# DBG_BOOT_CONF.net
KiCad netlist of a schematic drawn in Altium Designer
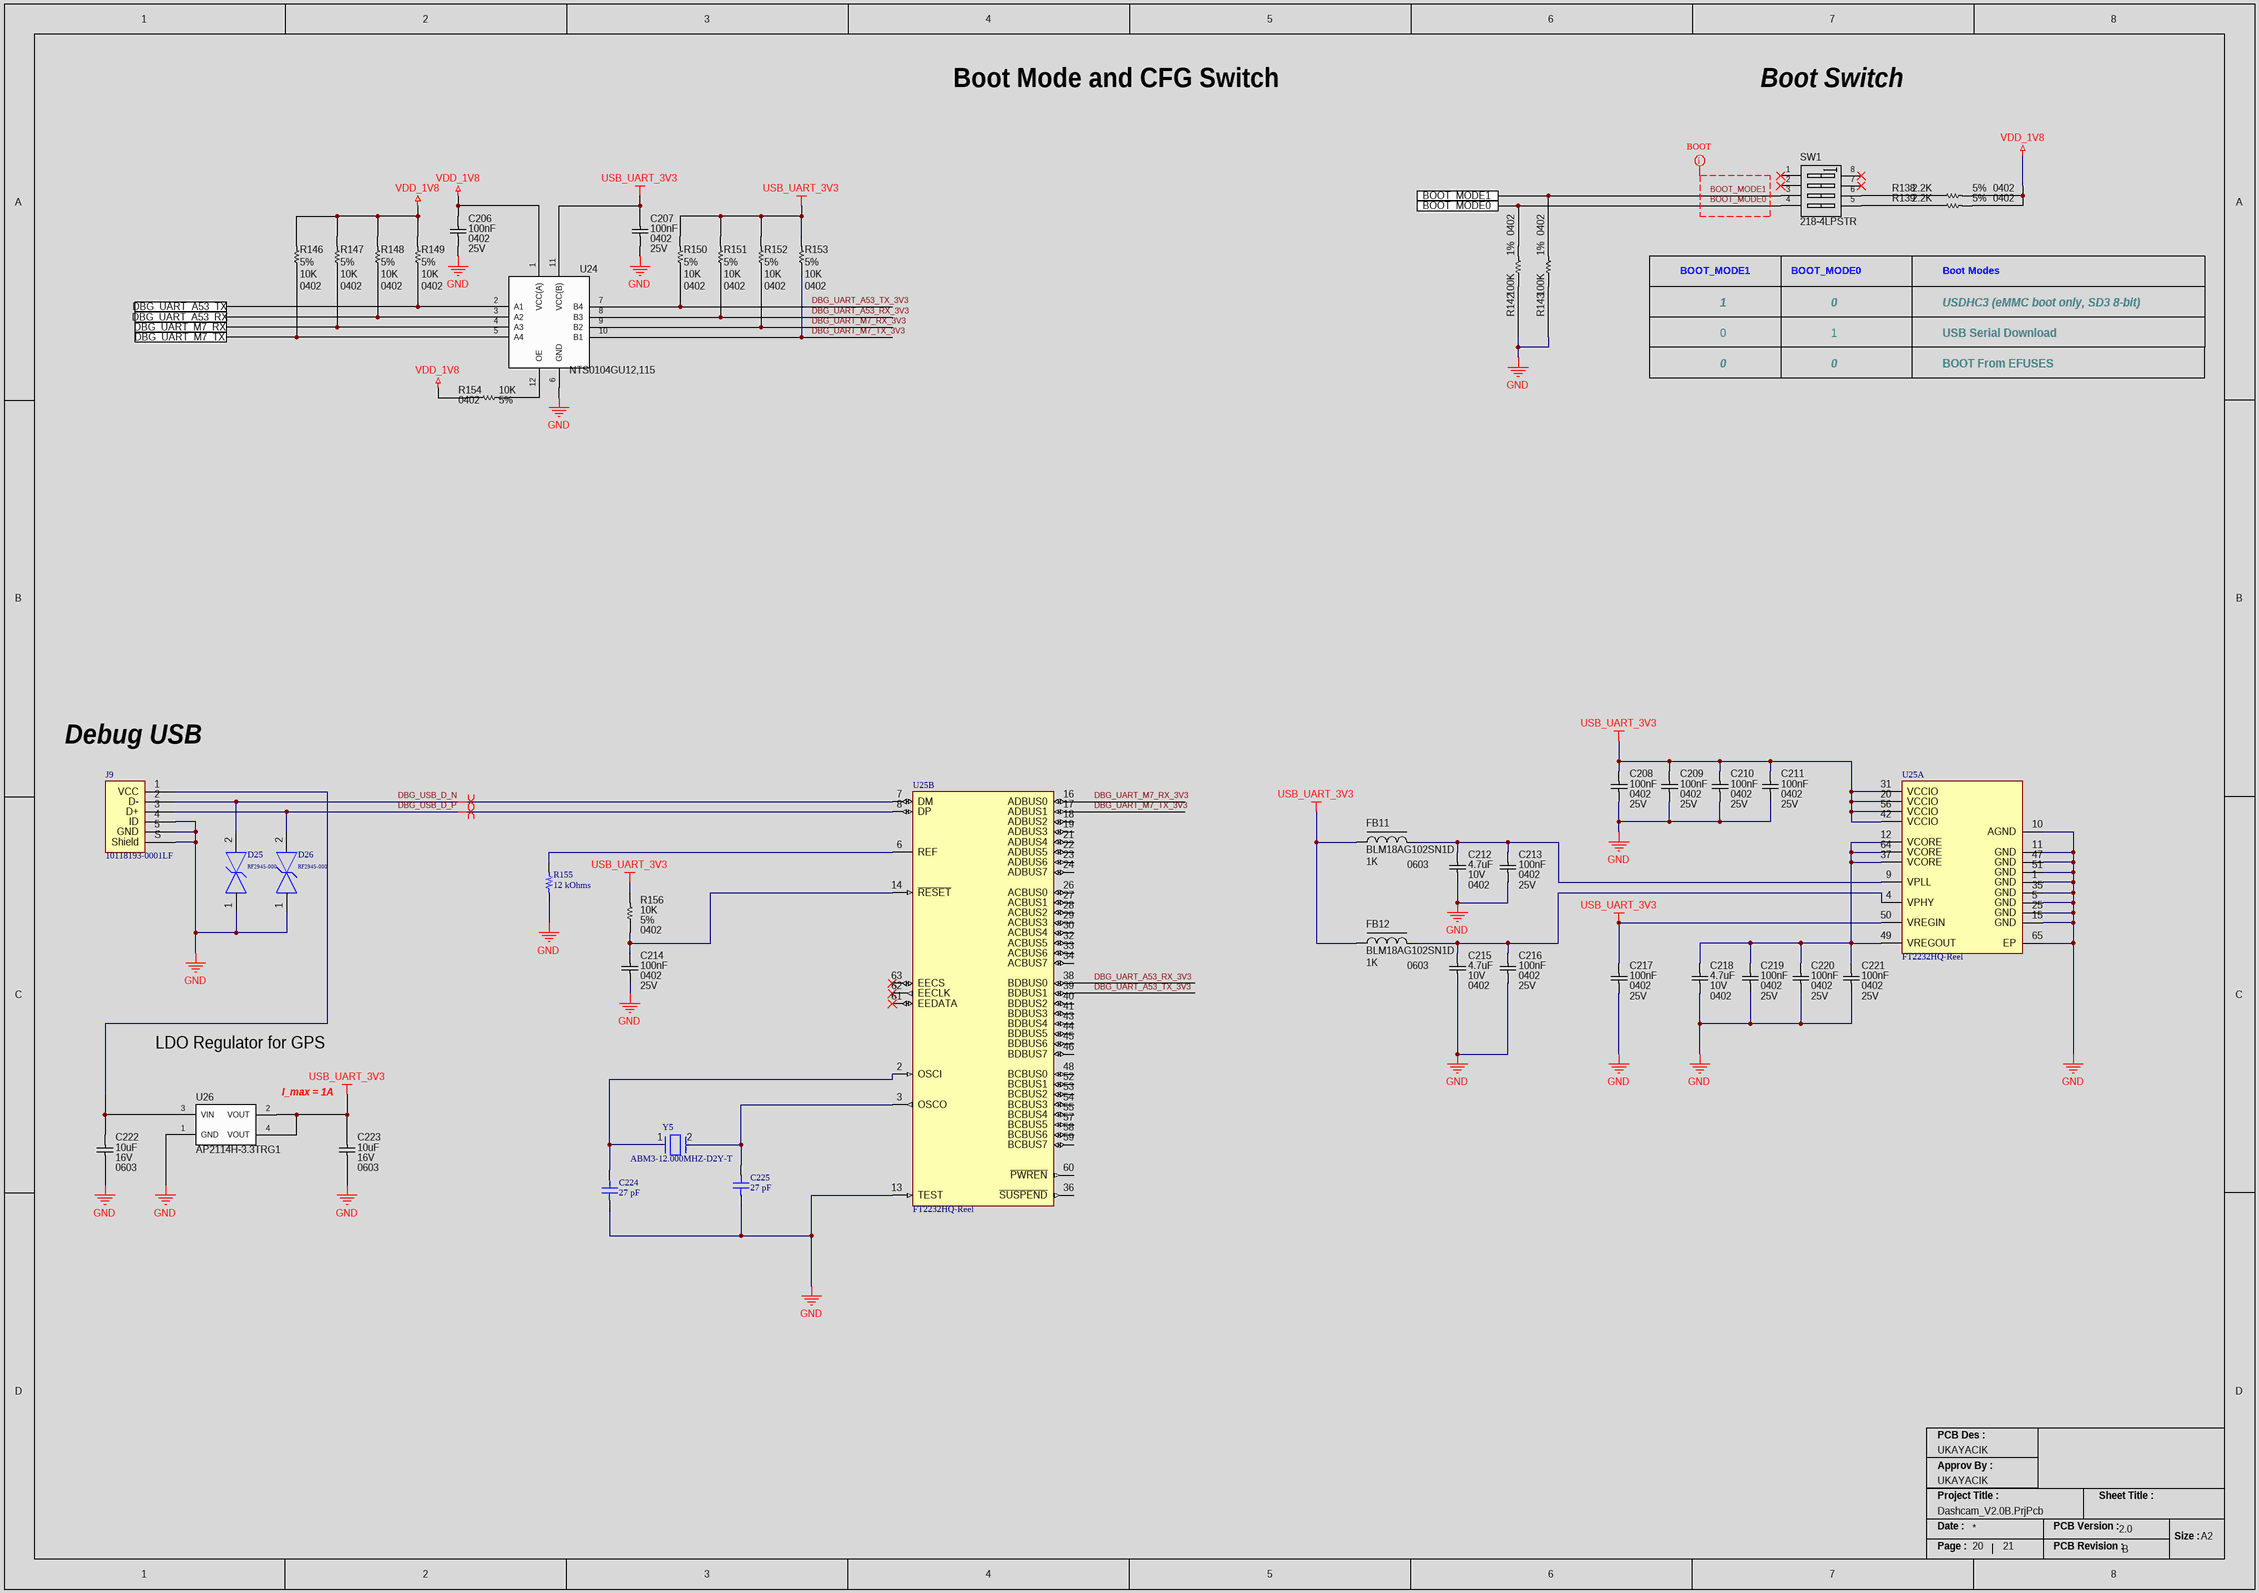
[diagram p0: DBG BOOT_CONF.SchDoc]

(export (version "E")
  (design (tool "Eeschema 10.0.6"))
  (components
    (comp (ref "C206")
      (value "CC0402KRX5R8BB104")
      (footprint "CAP_0402_CAPC1005X05N")
      (description "Multilayer Ceramic Capacitor, 0.1 uF, 25 V, ± 10%, X7R, 0402 [1005 Metric]")
      (fields
        (field (name "MANUFACTURER") "Yageo")
        (field (name "TOLERANCE") "10%")
        (field (name "CAPACITANCE") "100nF")
        (field (name "VOLTAGE RATING") "25V")
        (field (name "CASE/PACKAGE") "0402")
      )
      (libsource (lib "Electronic Devices_LIB") (part "CAP_100NF_25V_X7R_0402"))
    )
    (comp (ref "C207")
      (value "CC0402KRX5R8BB104")
      (footprint "CAP_0402_CAPC1005X05N")
      (description "Multilayer Ceramic Capacitor, 0.1 uF, 25 V, ± 10%, X7R, 0402 [1005 Metric]")
      (fields
        (field (name "MANUFACTURER") "Yageo")
        (field (name "TOLERANCE") "10%")
        (field (name "CAPACITANCE") "100nF")
        (field (name "VOLTAGE RATING") "25V")
        (field (name "CASE/PACKAGE") "0402")
      )
      (libsource (lib "Electronic Devices_LIB") (part "CAP_100NF_25V_X7R_0402"))
    )
    (comp (ref "C208")
      (value "CC0402KRX5R8BB104")
      (footprint "CAP_0402_CAPC1005X05N")
      (description "Multilayer Ceramic Capacitor, 0.1 uF, 25 V, ± 10%, X7R, 0402 [1005 Metric]")
      (fields
        (field (name "MANUFACTURER") "Yageo")
        (field (name "TOLERANCE") "10%")
        (field (name "CAPACITANCE") "100nF")
        (field (name "VOLTAGE RATING") "25V")
        (field (name "CASE/PACKAGE") "0402")
      )
      (libsource (lib "Electronic Devices_LIB") (part "CAP_100NF_25V_X7R_0402"))
    )
    (comp (ref "C209")
      (value "CC0402KRX5R8BB104")
      (footprint "CAP_0402_CAPC1005X05N")
      (description "Multilayer Ceramic Capacitor, 0.1 uF, 25 V, ± 10%, X7R, 0402 [1005 Metric]")
      (fields
        (field (name "MANUFACTURER") "Yageo")
        (field (name "TOLERANCE") "10%")
        (field (name "CAPACITANCE") "100nF")
        (field (name "VOLTAGE RATING") "25V")
        (field (name "CASE/PACKAGE") "0402")
      )
      (libsource (lib "Electronic Devices_LIB") (part "CAP_100NF_25V_X7R_0402"))
    )
    (comp (ref "C210")
      (value "CC0402KRX5R8BB104")
      (footprint "CAP_0402_CAPC1005X05N")
      (description "Multilayer Ceramic Capacitor, 0.1 uF, 25 V, ± 10%, X7R, 0402 [1005 Metric]")
      (fields
        (field (name "MANUFACTURER") "Yageo")
        (field (name "TOLERANCE") "10%")
        (field (name "CAPACITANCE") "100nF")
        (field (name "VOLTAGE RATING") "25V")
        (field (name "CASE/PACKAGE") "0402")
      )
      (libsource (lib "Electronic Devices_LIB") (part "CAP_100NF_25V_X7R_0402"))
    )
    (comp (ref "C211")
      (value "CC0402KRX5R8BB104")
      (footprint "CAP_0402_CAPC1005X05N")
      (description "Multilayer Ceramic Capacitor, 0.1 uF, 25 V, ± 10%, X7R, 0402 [1005 Metric]")
      (fields
        (field (name "MANUFACTURER") "Yageo")
        (field (name "TOLERANCE") "10%")
        (field (name "CAPACITANCE") "100nF")
        (field (name "VOLTAGE RATING") "25V")
        (field (name "CASE/PACKAGE") "0402")
      )
      (libsource (lib "Electronic Devices_LIB") (part "CAP_100NF_25V_X7R_0402"))
    )
    (comp (ref "C212")
      (value "CL05A475KP5NRNC")
      (footprint "CAP_0402_CAPC1005X05N")
      (description "Multilayer Ceramic Capacitor, 4.7 uF, 10 V, ± 10%, X5R, 0402 [1005 Metric]")
      (fields
        (field (name "MANUFACTURER") "Samsung")
        (field (name "TOLERANCE") "10%")
        (field (name "CAPACITANCE") "4.7uF")
        (field (name "VOLTAGE RATING") "10V")
        (field (name "CASE/PACKAGE") "0402")
      )
      (libsource (lib "Electronic Devices_LIB") (part "CAP_4.7UF_10V_X5R_0402"))
    )
    (comp (ref "C213")
      (value "CC0402KRX5R8BB104")
      (footprint "CAP_0402_CAPC1005X05N")
      (description "Multilayer Ceramic Capacitor, 0.1 uF, 25 V, ± 10%, X7R, 0402 [1005 Metric]")
      (fields
        (field (name "MANUFACTURER") "Yageo")
        (field (name "TOLERANCE") "10%")
        (field (name "CAPACITANCE") "100nF")
        (field (name "VOLTAGE RATING") "25V")
        (field (name "CASE/PACKAGE") "0402")
      )
      (libsource (lib "Electronic Devices_LIB") (part "CAP_100NF_25V_X7R_0402"))
    )
    (comp (ref "C214")
      (value "CC0402KRX5R8BB104")
      (footprint "CAP_0402_CAPC1005X05N")
      (description "Multilayer Ceramic Capacitor, 0.1 uF, 25 V, ± 10%, X7R, 0402 [1005 Metric]")
      (fields
        (field (name "MANUFACTURER") "Yageo")
        (field (name "TOLERANCE") "10%")
        (field (name "CAPACITANCE") "100nF")
        (field (name "VOLTAGE RATING") "25V")
        (field (name "CASE/PACKAGE") "0402")
      )
      (libsource (lib "Electronic Devices_LIB") (part "CAP_100NF_25V_X7R_0402"))
    )
    (comp (ref "C215")
      (value "CL05A475KP5NRNC")
      (footprint "CAP_0402_CAPC1005X05N")
      (description "Multilayer Ceramic Capacitor, 4.7 uF, 10 V, ± 10%, X5R, 0402 [1005 Metric]")
      (fields
        (field (name "MANUFACTURER") "Samsung")
        (field (name "TOLERANCE") "10%")
        (field (name "CAPACITANCE") "4.7uF")
        (field (name "VOLTAGE RATING") "10V")
        (field (name "CASE/PACKAGE") "0402")
      )
      (libsource (lib "Electronic Devices_LIB") (part "CAP_4.7UF_10V_X5R_0402"))
    )
    (comp (ref "C216")
      (value "CC0402KRX5R8BB104")
      (footprint "CAP_0402_CAPC1005X05N")
      (description "Multilayer Ceramic Capacitor, 0.1 uF, 25 V, ± 10%, X7R, 0402 [1005 Metric]")
      (fields
        (field (name "MANUFACTURER") "Yageo")
        (field (name "TOLERANCE") "10%")
        (field (name "CAPACITANCE") "100nF")
        (field (name "VOLTAGE RATING") "25V")
        (field (name "CASE/PACKAGE") "0402")
      )
      (libsource (lib "Electronic Devices_LIB") (part "CAP_100NF_25V_X7R_0402"))
    )
    (comp (ref "C217")
      (value "CC0402KRX5R8BB104")
      (footprint "CAP_0402_CAPC1005X05N")
      (description "Multilayer Ceramic Capacitor, 0.1 uF, 25 V, ± 10%, X7R, 0402 [1005 Metric]")
      (fields
        (field (name "MANUFACTURER") "Yageo")
        (field (name "TOLERANCE") "10%")
        (field (name "CAPACITANCE") "100nF")
        (field (name "VOLTAGE RATING") "25V")
        (field (name "CASE/PACKAGE") "0402")
      )
      (libsource (lib "Electronic Devices_LIB") (part "CAP_100NF_25V_X7R_0402"))
    )
    (comp (ref "C218")
      (value "CL05A475KP5NRNC")
      (footprint "CAP_0402_CAPC1005X05N")
      (description "Multilayer Ceramic Capacitor, 4.7 uF, 10 V, ± 10%, X5R, 0402 [1005 Metric]")
      (fields
        (field (name "MANUFACTURER") "Samsung")
        (field (name "TOLERANCE") "10%")
        (field (name "CAPACITANCE") "4.7uF")
        (field (name "VOLTAGE RATING") "10V")
        (field (name "CASE/PACKAGE") "0402")
      )
      (libsource (lib "Electronic Devices_LIB") (part "CAP_4.7UF_10V_X5R_0402"))
    )
    (comp (ref "C219")
      (value "CC0402KRX5R8BB104")
      (footprint "CAP_0402_CAPC1005X05N")
      (description "Multilayer Ceramic Capacitor, 0.1 uF, 25 V, ± 10%, X7R, 0402 [1005 Metric]")
      (fields
        (field (name "MANUFACTURER") "Yageo")
        (field (name "TOLERANCE") "10%")
        (field (name "CAPACITANCE") "100nF")
        (field (name "VOLTAGE RATING") "25V")
        (field (name "CASE/PACKAGE") "0402")
      )
      (libsource (lib "Electronic Devices_LIB") (part "CAP_100NF_25V_X7R_0402"))
    )
    (comp (ref "C220")
      (value "CC0402KRX5R8BB104")
      (footprint "CAP_0402_CAPC1005X05N")
      (description "Multilayer Ceramic Capacitor, 0.1 uF, 25 V, ± 10%, X7R, 0402 [1005 Metric]")
      (fields
        (field (name "MANUFACTURER") "Yageo")
        (field (name "TOLERANCE") "10%")
        (field (name "CAPACITANCE") "100nF")
        (field (name "VOLTAGE RATING") "25V")
        (field (name "CASE/PACKAGE") "0402")
      )
      (libsource (lib "Electronic Devices_LIB") (part "CAP_100NF_25V_X7R_0402"))
    )
    (comp (ref "C221")
      (value "CC0402KRX5R8BB104")
      (footprint "CAP_0402_CAPC1005X05N")
      (description "Multilayer Ceramic Capacitor, 0.1 uF, 25 V, ± 10%, X7R, 0402 [1005 Metric]")
      (fields
        (field (name "MANUFACTURER") "Yageo")
        (field (name "TOLERANCE") "10%")
        (field (name "CAPACITANCE") "100nF")
        (field (name "VOLTAGE RATING") "25V")
        (field (name "CASE/PACKAGE") "0402")
      )
      (libsource (lib "Electronic Devices_LIB") (part "CAP_100NF_25V_X7R_0402"))
    )
    (comp (ref "C222")
      (value "GRM188R61C106MAALD")
      (footprint "CAP_0603_CAPC1608X08N")
      (description "0603 10 uF 16 V ±20% Tolerance X5R Multilayer Ceramic Chip Capacitor")
      (fields
        (field (name "MANUFACTURER") "Murata")
        (field (name "TOLERANCE") "20%")
        (field (name "VOLTAGE RATING") "16V")
        (field (name "CAPACITANCE") "10uF")
        (field (name "CASE/PACKAGE") "0603")
      )
      (libsource (lib "Electronic Devices_LIB") (part "CAP_10UF_16V_X5R_0603"))
    )
    (comp (ref "C223")
      (value "GRM188R61C106MAALD")
      (footprint "CAP_0603_CAPC1608X08N")
      (description "0603 10 uF 16 V ±20% Tolerance X5R Multilayer Ceramic Chip Capacitor")
      (fields
        (field (name "MANUFACTURER") "Murata")
        (field (name "TOLERANCE") "20%")
        (field (name "VOLTAGE RATING") "16V")
        (field (name "CAPACITANCE") "10uF")
        (field (name "CASE/PACKAGE") "0603")
      )
      (libsource (lib "Electronic Devices_LIB") (part "CAP_10UF_16V_X5R_0603"))
    )
    (comp (ref "C224")
      (value "27 pF")
      (footprint "CAP 0402_1005")
      (description "CAP CER 27PF 25V C0G/NP0 0402")
      (fields
        (field (name "PART NUMBER") "0402N270J250CT")
        (field (name "CAPACITANCE") "27 pF")
        (field (name "MANUFACTURER") "Walsin Technology Corporation")
      )
      (libsource (lib "Celestial Altium Library - altium_library") (part "Capacitor"))
    )
    (comp (ref "C225")
      (value "27 pF")
      (footprint "CAP 0402_1005")
      (description "CAP CER 27PF 25V C0G/NP0 0402")
      (fields
        (field (name "PART NUMBER") "0402N270J250CT")
        (field (name "CAPACITANCE") "27 pF")
        (field (name "MANUFACTURER") "Walsin Technology Corporation")
      )
      (libsource (lib "Celestial Altium Library - altium_library") (part "Capacitor"))
    )
    (comp (ref "D25")
      (value "RF2945-000")
      (footprint "FP-SESD0402-MFG")
      (description "TVS DIODE 7V 10V 0402")
      (fields
        (field (name "OCTOPART") "https://octopart.com/rf2945-000-littelfuse-56516902")
        (field (name "MANUFACTURER") "Littelfuse")
      )
      (libsource (lib "Altium Content Vault") (part "876f4347bf90aa6f500f43e3cd03972"))
    )
    (comp (ref "D26")
      (value "RF2945-000")
      (footprint "FP-SESD0402-MFG")
      (description "TVS DIODE 7V 10V 0402")
      (fields
        (field (name "OCTOPART") "https://octopart.com/rf2945-000-littelfuse-56516902")
        (field (name "MANUFACTURER") "Littelfuse")
      )
      (libsource (lib "Altium Content Vault") (part "876f4347bf90aa6f500f43e3cd03972"))
    )
    (comp (ref "FB11")
      (value "BLM18AG102SN1D")
      (footprint "IND_0603_INDC1608X08N")
      (description "Ferrite Beads Multi-Layer 1KOhm 25% 100MHz 450mA 500mOhm DCR 0603 T/R")
      (fields
        (field (name "MANUFACTURER") "Murata")
        (field (name "TOLERANCE") "25%")
        (field (name "IMPEDANCE") "1K")
        (field (name "CASE/PACKAGE") "0603")
      )
      (libsource (lib "Electronic Devices_LIB") (part "IND_FERRITA_1K_450mA_BLM18AG102SN1D"))
    )
    (comp (ref "FB12")
      (value "BLM18AG102SN1D")
      (footprint "IND_0603_INDC1608X08N")
      (description "Ferrite Beads Multi-Layer 1KOhm 25% 100MHz 450mA 500mOhm DCR 0603 T/R")
      (fields
        (field (name "MANUFACTURER") "Murata")
        (field (name "TOLERANCE") "25%")
        (field (name "IMPEDANCE") "1K")
        (field (name "CASE/PACKAGE") "0603")
      )
      (libsource (lib "Electronic Devices_LIB") (part "IND_FERRITA_1K_450mA_BLM18AG102SN1D"))
    )
    (comp (ref "J9")
      (value "10118193-0001LF")
      (footprint "FCI USB 10118193-0001LF")
      (description "CONN RCPT USB2.0 MICRO B SMD R/A")
      (fields (field (name "MANUFACTURER") "Amphenol ICC (FCI)"))
      (libsource (lib "Celestial Altium Library - altium_library") (part "USB 2.0 Type B Micro"))
    )
    (comp (ref "R138")
      (value "RC0402JR-072K2L")
      (footprint "RES_0402_RESC1005X04N")
      (description "SMD Chip Resistor, 2.2 kOhm, ± 5%, 63 mW, 0402 [1005 Metric], Thick Film, General Purpose")
      (fields
        (field (name "MANUFACTURER") "Yageo")
        (field (name "TOLERANCE") "5%")
        (field (name "RESISTANCE") "2.2K")
        (field (name "CASE/PACKAGE") "0402")
      )
      (libsource (lib "Electronic Devices_LIB") (part "RES_2.2K_5%_63mW_0402"))
    )
    (comp (ref "R139")
      (value "RC0402JR-072K2L")
      (footprint "RES_0402_RESC1005X04N")
      (description "SMD Chip Resistor, 2.2 kOhm, ± 5%, 63 mW, 0402 [1005 Metric], Thick Film, General Purpose")
      (fields
        (field (name "MANUFACTURER") "Yageo")
        (field (name "TOLERANCE") "5%")
        (field (name "RESISTANCE") "2.2K")
        (field (name "CASE/PACKAGE") "0402")
      )
      (libsource (lib "Electronic Devices_LIB") (part "RES_2.2K_5%_63mW_0402"))
    )
    (comp (ref "R142")
      (value "RC0402FR-07100KL")
      (footprint "RES_0402_RESC1005X04N")
      (description "SMD Chip Resistor, 100 kOhm, ± 1%, 63 mW, 0402 [1005 Metric], Thick Film, General Purpose")
      (fields
        (field (name "MANUFACTURER") "Yageo")
        (field (name "RESISTANCE") "100K")
        (field (name "TOLERANCE") "1%")
        (field (name "CASE/PACKAGE") "0402")
      )
      (libsource (lib "Electronic Devices_LIB") (part "RES_100K_1%_100mW_0402"))
    )
    (comp (ref "R143")
      (value "RC0402FR-07100KL")
      (footprint "RES_0402_RESC1005X04N")
      (description "SMD Chip Resistor, 100 kOhm, ± 1%, 63 mW, 0402 [1005 Metric], Thick Film, General Purpose")
      (fields
        (field (name "MANUFACTURER") "Yageo")
        (field (name "RESISTANCE") "100K")
        (field (name "TOLERANCE") "1%")
        (field (name "CASE/PACKAGE") "0402")
      )
      (libsource (lib "Electronic Devices_LIB") (part "RES_100K_1%_100mW_0402"))
    )
    (comp (ref "R146")
      (value "ERJ-2GEJ103X")
      (footprint "RES_0402_RESC1005X04N")
      (description "Res Thick Film 0402 10K Ohm 5% 1/10W ±200ppm/°C Molded SMD Punched Carrier T/R")
      (fields
        (field (name "MANUFACTURER") "Panasonic")
        (field (name "TOLERANCE") "5%")
        (field (name "RESISTANCE") "10K")
        (field (name "CASE/PACKAGE") "0402")
      )
      (libsource (lib "Electronic Devices_LIB") (part "RES_10K_5%_100mW_0402"))
    )
    (comp (ref "R147")
      (value "ERJ-2GEJ103X")
      (footprint "RES_0402_RESC1005X04N")
      (description "Res Thick Film 0402 10K Ohm 5% 1/10W ±200ppm/°C Molded SMD Punched Carrier T/R")
      (fields
        (field (name "MANUFACTURER") "Panasonic")
        (field (name "TOLERANCE") "5%")
        (field (name "RESISTANCE") "10K")
        (field (name "CASE/PACKAGE") "0402")
      )
      (libsource (lib "Electronic Devices_LIB") (part "RES_10K_5%_100mW_0402"))
    )
    (comp (ref "R148")
      (value "ERJ-2GEJ103X")
      (footprint "RES_0402_RESC1005X04N")
      (description "Res Thick Film 0402 10K Ohm 5% 1/10W ±200ppm/°C Molded SMD Punched Carrier T/R")
      (fields
        (field (name "MANUFACTURER") "Panasonic")
        (field (name "TOLERANCE") "5%")
        (field (name "RESISTANCE") "10K")
        (field (name "CASE/PACKAGE") "0402")
      )
      (libsource (lib "Electronic Devices_LIB") (part "RES_10K_5%_100mW_0402"))
    )
    (comp (ref "R149")
      (value "ERJ-2GEJ103X")
      (footprint "RES_0402_RESC1005X04N")
      (description "Res Thick Film 0402 10K Ohm 5% 1/10W ±200ppm/°C Molded SMD Punched Carrier T/R")
      (fields
        (field (name "MANUFACTURER") "Panasonic")
        (field (name "TOLERANCE") "5%")
        (field (name "RESISTANCE") "10K")
        (field (name "CASE/PACKAGE") "0402")
      )
      (libsource (lib "Electronic Devices_LIB") (part "RES_10K_5%_100mW_0402"))
    )
    (comp (ref "R150")
      (value "ERJ-2GEJ103X")
      (footprint "RES_0402_RESC1005X04N")
      (description "Res Thick Film 0402 10K Ohm 5% 1/10W ±200ppm/°C Molded SMD Punched Carrier T/R")
      (fields
        (field (name "MANUFACTURER") "Panasonic")
        (field (name "TOLERANCE") "5%")
        (field (name "RESISTANCE") "10K")
        (field (name "CASE/PACKAGE") "0402")
      )
      (libsource (lib "Electronic Devices_LIB") (part "RES_10K_5%_100mW_0402"))
    )
    (comp (ref "R151")
      (value "ERJ-2GEJ103X")
      (footprint "RES_0402_RESC1005X04N")
      (description "Res Thick Film 0402 10K Ohm 5% 1/10W ±200ppm/°C Molded SMD Punched Carrier T/R")
      (fields
        (field (name "MANUFACTURER") "Panasonic")
        (field (name "TOLERANCE") "5%")
        (field (name "RESISTANCE") "10K")
        (field (name "CASE/PACKAGE") "0402")
      )
      (libsource (lib "Electronic Devices_LIB") (part "RES_10K_5%_100mW_0402"))
    )
    (comp (ref "R152")
      (value "ERJ-2GEJ103X")
      (footprint "RES_0402_RESC1005X04N")
      (description "Res Thick Film 0402 10K Ohm 5% 1/10W ±200ppm/°C Molded SMD Punched Carrier T/R")
      (fields
        (field (name "MANUFACTURER") "Panasonic")
        (field (name "TOLERANCE") "5%")
        (field (name "RESISTANCE") "10K")
        (field (name "CASE/PACKAGE") "0402")
      )
      (libsource (lib "Electronic Devices_LIB") (part "RES_10K_5%_100mW_0402"))
    )
    (comp (ref "R153")
      (value "ERJ-2GEJ103X")
      (footprint "RES_0402_RESC1005X04N")
      (description "Res Thick Film 0402 10K Ohm 5% 1/10W ±200ppm/°C Molded SMD Punched Carrier T/R")
      (fields
        (field (name "MANUFACTURER") "Panasonic")
        (field (name "TOLERANCE") "5%")
        (field (name "RESISTANCE") "10K")
        (field (name "CASE/PACKAGE") "0402")
      )
      (libsource (lib "Electronic Devices_LIB") (part "RES_10K_5%_100mW_0402"))
    )
    (comp (ref "R154")
      (value "ERJ-2GEJ103X")
      (footprint "RES_0402_RESC1005X04N")
      (description "Res Thick Film 0402 10K Ohm 5% 1/10W ±200ppm/°C Molded SMD Punched Carrier T/R")
      (fields
        (field (name "MANUFACTURER") "Panasonic")
        (field (name "TOLERANCE") "5%")
        (field (name "RESISTANCE") "10K")
        (field (name "CASE/PACKAGE") "0402")
      )
      (libsource (lib "Electronic Devices_LIB") (part "RES_10K_5%_100mW_0402"))
    )
    (comp (ref "R155")
      (value "12 kOhms")
      (footprint "RES 0402_1005")
      (description "RES 12K OHM 1% 1/16W 0402")
      (fields
        (field (name "PART NUMBER") "RMCF0402FT12K0")
        (field (name "MANUFACTURER") "Stackpole Electronics Inc")
      )
      (libsource (lib "Celestial Altium Library - altium_library") (part "Resistor"))
    )
    (comp (ref "R156")
      (value "ERJ-2GEJ103X")
      (footprint "RES_0402_RESC1005X04N")
      (description "Res Thick Film 0402 10K Ohm 5% 1/10W ±200ppm/°C Molded SMD Punched Carrier T/R")
      (fields
        (field (name "MANUFACTURER") "Panasonic")
        (field (name "TOLERANCE") "5%")
        (field (name "RESISTANCE") "10K")
        (field (name "CASE/PACKAGE") "0402")
      )
      (libsource (lib "Electronic Devices_LIB") (part "RES_10K_5%_100mW_0402"))
    )
    (comp (ref "SW1")
      (value "218-4LPSTR")
      (footprint "SW_DIP_SOIC127P844X265-8N")
      (description "Switch DIP ON OFF SPST 4 Recessed Slide 0.025A 24VDC Gull Wing 1000Cycles 1.27mm SMD T/R")
      (fields (field (name "MANUFACTURER") "CTS"))
      (libsource (lib "Electronic Devices_LIB") (part "SWITCH_DIP_4P_25mA_218-4LPSTR"))
    )
    (comp (ref "U24")
      (value "NTS0104GU12,115")
      (footprint "IC_LEVEL_TRASLATOR_XQFN12_0P4_1P8X2P1")
      (description "NTS0104 Series 50 Mbps Dual Supply 3-ST O-DRN Translating Transceiver- XQFN-12")
      (fields (field (name "MANUFACTURER") "NXP Semiconductors"))
      (libsource (lib "Electronic Devices_LIB") (part "IC_LEVEL_TRASLATOR_NTS0104GU12,115"))
    )
    (comp (ref "U25")
      (value "FT2232HQ-Reel")
      (footprint "FP-FT2232HQ-Reel-MFG")
      (description "IC USB HS DUAL UART/FIFO 64-QFN")
      (fields
        (field (name "OCTOPART") "https://octopart.com/ft2232hq-reel-ftdi-19172126")
        (field (name "MANUFACTURER") "FTDI")
      )
      (libsource (lib "Altium Content Vault") (part "69ab9ac86b67af101dfdf5de5064102"))
    )
    (comp (ref "U26")
      (value "AP2114H-3.3TRG1")
      (footprint "IC_REG_SOT230P700X180-4N")
      (description "IC REG LDO 3.3V 1A SOT223")
      (fields (field (name "MANUFACTURER") "Diodes"))
      (libsource (lib "Electronic Devices_LIB") (part "IC_REG_LDO_3.3V_1A_AP2114H-3.3TRG1"))
    )
    (comp (ref "Y5")
      (value "ABM3-12.000MHZ-D2Y-T")
      (footprint "FP-ABM3-MFG")
      (description "Crystal 12MHz ±20ppm 18pF SMD-2 5mm x 3.2mm")
      (fields (field (name "TOLERANCE") "20ppm"))
      (libsource (lib "Altium Content Vault") (part "c23a69dc6c9e2f18f2079038eb95dd1"))
    )
  )
  (nets
    (net (code "1") (name "/BOOT_MODE0") (class "Default")
      (node (ref "R142") (pin "2") (pinfunction "2_2") (pintype "passive"))
      (node (ref "SW1") (pin "4") (pinfunction "A4_4") (pintype "passive"))
    )
    (net (code "2") (name "/BOOT_MODE1") (class "Default")
      (node (ref "R143") (pin "2") (pinfunction "2_2") (pintype "passive"))
      (node (ref "SW1") (pin "3") (pinfunction "A3_3") (pintype "passive"))
    )
    (net (code "3") (name "/DBG_UART_A53_RX") (class "Default")
      (node (ref "R148") (pin "1") (pinfunction "1_1") (pintype "passive"))
      (node (ref "U24") (pin "3") (pinfunction "A2_3") (pintype "passive"))
    )
    (net (code "4") (name "/DBG_UART_A53_RX_3V3") (class "Default")
      (node (ref "R151") (pin "1") (pinfunction "1_1") (pintype "passive"))
      (node (ref "U24") (pin "8") (pinfunction "B3_8") (pintype "passive"))
      (node (ref "U25") (pin "38") (pinfunction "BDBUS0_38") (pintype "bidirectional"))
    )
    (net (code "5") (name "/DBG_UART_A53_TX") (class "Default")
      (node (ref "R149") (pin "1") (pinfunction "1_1") (pintype "passive"))
      (node (ref "U24") (pin "2") (pinfunction "A1_2") (pintype "passive"))
    )
    (net (code "6") (name "/DBG_UART_A53_TX_3V3") (class "Default")
      (node (ref "R150") (pin "1") (pinfunction "1_1") (pintype "passive"))
      (node (ref "U24") (pin "7") (pinfunction "B4_7") (pintype "passive"))
      (node (ref "U25") (pin "39") (pinfunction "BDBUS1_39") (pintype "bidirectional"))
    )
    (net (code "7") (name "/DBG_UART_M7_RX") (class "Default")
      (node (ref "R147") (pin "1") (pinfunction "1_1") (pintype "passive"))
      (node (ref "U24") (pin "4") (pinfunction "A3_4") (pintype "passive"))
    )
    (net (code "8") (name "/DBG_UART_M7_RX_3V3") (class "Default")
      (node (ref "R152") (pin "1") (pinfunction "1_1") (pintype "passive"))
      (node (ref "U24") (pin "9") (pinfunction "B2_9") (pintype "passive"))
      (node (ref "U25") (pin "16") (pinfunction "ADBUS0_16") (pintype "bidirectional"))
    )
    (net (code "9") (name "/DBG_UART_M7_TX") (class "Default")
      (node (ref "R146") (pin "1") (pinfunction "1_1") (pintype "passive"))
      (node (ref "U24") (pin "5") (pinfunction "A4_5") (pintype "passive"))
    )
    (net (code "10") (name "/DBG_UART_M7_TX_3V3") (class "Default")
      (node (ref "R153") (pin "1") (pinfunction "1_1") (pintype "passive"))
      (node (ref "U24") (pin "10") (pinfunction "B1_10") (pintype "passive"))
      (node (ref "U25") (pin "17") (pinfunction "ADBUS1_17") (pintype "bidirectional"))
    )
    (net (code "11") (name "/DBG_USB_D_N") (class "Default")
      (node (ref "D25") (pin "2") (pinfunction "2_2") (pintype "passive"))
      (node (ref "J9") (pin "2") (pinfunction "D-_2") (pintype "passive"))
      (node (ref "U25") (pin "7") (pinfunction "DM_7") (pintype "bidirectional"))
    )
    (net (code "12") (name "/DBG_USB_D_P") (class "Default")
      (node (ref "D26") (pin "2") (pinfunction "2_2") (pintype "passive"))
      (node (ref "J9") (pin "3") (pinfunction "D+_3") (pintype "passive"))
      (node (ref "U25") (pin "8") (pinfunction "DP_8") (pintype "bidirectional"))
    )
    (net (code "13") (name "GND") (class "Default")
      (node (ref "C206") (pin "1") (pinfunction "1_1") (pintype "passive"))
      (node (ref "C207") (pin "1") (pinfunction "1_1") (pintype "passive"))
      (node (ref "C208") (pin "1") (pinfunction "1_1") (pintype "passive"))
      (node (ref "C209") (pin "1") (pinfunction "1_1") (pintype "passive"))
      (node (ref "C210") (pin "1") (pinfunction "1_1") (pintype "passive"))
      (node (ref "C211") (pin "1") (pinfunction "1_1") (pintype "passive"))
      (node (ref "C212") (pin "1") (pinfunction "1_1") (pintype "passive"))
      (node (ref "C213") (pin "1") (pinfunction "1_1") (pintype "passive"))
      (node (ref "C214") (pin "1") (pinfunction "1_1") (pintype "passive"))
      (node (ref "C215") (pin "1") (pinfunction "1_1") (pintype "passive"))
      (node (ref "C216") (pin "1") (pinfunction "1_1") (pintype "passive"))
      (node (ref "C217") (pin "1") (pinfunction "1_1") (pintype "passive"))
      (node (ref "C218") (pin "1") (pinfunction "1_1") (pintype "passive"))
      (node (ref "C219") (pin "1") (pinfunction "1_1") (pintype "passive"))
      (node (ref "C220") (pin "1") (pinfunction "1_1") (pintype "passive"))
      (node (ref "C221") (pin "1") (pinfunction "1_1") (pintype "passive"))
      (node (ref "C222") (pin "1") (pinfunction "1_1") (pintype "passive"))
      (node (ref "C223") (pin "1") (pinfunction "1_1") (pintype "passive"))
      (node (ref "C224") (pin "1") (pinfunction "1_1") (pintype "passive"))
      (node (ref "C225") (pin "1") (pinfunction "1_1") (pintype "passive"))
      (node (ref "D25") (pin "1") (pinfunction "1_1") (pintype "passive"))
      (node (ref "D26") (pin "1") (pinfunction "1_1") (pintype "passive"))
      (node (ref "J9") (pin "4") (pinfunction "ID_4") (pintype "passive"))
      (node (ref "J9") (pin "5") (pinfunction "GND_5") (pintype "passive"))
      (node (ref "J9") (pin "S") (pinfunction "Shield_S") (pintype "passive"))
      (node (ref "R142") (pin "1") (pinfunction "1_1") (pintype "passive"))
      (node (ref "R143") (pin "1") (pinfunction "1_1") (pintype "passive"))
      (node (ref "R155") (pin "1") (pinfunction "1_1") (pintype "passive"))
      (node (ref "U24") (pin "6") (pinfunction "GND_6") (pintype "passive"))
      (node (ref "U25") (pin "1") (pinfunction "GND_1") (pintype "power_in"))
      (node (ref "U25") (pin "10") (pinfunction "AGND_10") (pintype "power_in"))
      (node (ref "U25") (pin "11") (pinfunction "GND_11") (pintype "power_in"))
      (node (ref "U25") (pin "13") (pinfunction "TEST_13") (pintype "input"))
      (node (ref "U25") (pin "15") (pinfunction "GND_15") (pintype "power_in"))
      (node (ref "U25") (pin "25") (pinfunction "GND_25") (pintype "power_in"))
      (node (ref "U25") (pin "35") (pinfunction "GND_35") (pintype "power_in"))
      (node (ref "U25") (pin "47") (pinfunction "GND_47") (pintype "power_in"))
      (node (ref "U25") (pin "5") (pinfunction "GND_5") (pintype "power_in"))
      (node (ref "U25") (pin "51") (pinfunction "GND_51") (pintype "power_in"))
      (node (ref "U25") (pin "65") (pinfunction "EP_65") (pintype "passive"))
      (node (ref "U26") (pin "1") (pinfunction "GND_1") (pintype "passive"))
    )
    (net (code "14") (name "Net-(J9-VCC)") (class "Default")
      (node (ref "C222") (pin "2") (pinfunction "2_2") (pintype "passive"))
      (node (ref "J9") (pin "1") (pinfunction "VCC_1") (pintype "passive"))
      (node (ref "U26") (pin "3") (pinfunction "VIN_3") (pintype "passive"))
    )
    (net (code "15") (name "Net-(SW1-B3)") (class "Default")
      (node (ref "R138") (pin "1") (pinfunction "1_1") (pintype "passive"))
      (node (ref "SW1") (pin "6") (pinfunction "B3_6") (pintype "passive"))
    )
    (net (code "16") (name "Net-(SW1-B4)") (class "Default")
      (node (ref "R139") (pin "1") (pinfunction "1_1") (pintype "passive"))
      (node (ref "SW1") (pin "5") (pinfunction "B4_5") (pintype "passive"))
    )
    (net (code "17") (name "Net-(U24-OE)") (class "Default")
      (node (ref "R154") (pin "2") (pinfunction "2_2") (pintype "passive"))
      (node (ref "U24") (pin "12") (pinfunction "OE_12") (pintype "passive"))
    )
    (net (code "18") (name "Net-(U25A-VPHY)") (class "Default")
      (node (ref "C215") (pin "2") (pinfunction "2_2") (pintype "passive"))
      (node (ref "C216") (pin "2") (pinfunction "2_2") (pintype "passive"))
      (node (ref "FB12") (pin "2") (pinfunction "2_2") (pintype "passive"))
      (node (ref "U25") (pin "4") (pinfunction "VPHY_4") (pintype "power_in"))
    )
    (net (code "19") (name "Net-(U25A-VPLL)") (class "Default")
      (node (ref "C212") (pin "2") (pinfunction "2_2") (pintype "passive"))
      (node (ref "C213") (pin "2") (pinfunction "2_2") (pintype "passive"))
      (node (ref "FB11") (pin "2") (pinfunction "2_2") (pintype "passive"))
      (node (ref "U25") (pin "9") (pinfunction "VPLL_9") (pintype "power_in"))
    )
    (net (code "20") (name "Net-(U25A-VREGOUT)") (class "Default")
      (node (ref "C218") (pin "2") (pinfunction "2_2") (pintype "passive"))
      (node (ref "C219") (pin "2") (pinfunction "2_2") (pintype "passive"))
      (node (ref "C220") (pin "2") (pinfunction "2_2") (pintype "passive"))
      (node (ref "C221") (pin "2") (pinfunction "2_2") (pintype "passive"))
      (node (ref "U25") (pin "12") (pinfunction "VCORE_12") (pintype "power_in"))
      (node (ref "U25") (pin "37") (pinfunction "VCORE_37") (pintype "power_in"))
      (node (ref "U25") (pin "49") (pinfunction "VREGOUT_49") (pintype "power_in"))
      (node (ref "U25") (pin "64") (pinfunction "VCORE_64") (pintype "power_in"))
    )
    (net (code "21") (name "Net-(U25B-OSCI)") (class "Default")
      (node (ref "C224") (pin "2") (pinfunction "2_2") (pintype "passive"))
      (node (ref "U25") (pin "2") (pinfunction "OSCI_2") (pintype "input"))
      (node (ref "Y5") (pin "1") (pinfunction "1_1") (pintype "passive"))
    )
    (net (code "22") (name "Net-(U25B-OSCO)") (class "Default")
      (node (ref "C225") (pin "2") (pinfunction "2_2") (pintype "passive"))
      (node (ref "U25") (pin "3") (pinfunction "OSCO_3") (pintype "output"))
      (node (ref "Y5") (pin "2") (pinfunction "2_2") (pintype "passive"))
    )
    (net (code "23") (name "Net-(U25B-REF)") (class "Default")
      (node (ref "R155") (pin "2") (pinfunction "2_2") (pintype "passive"))
      (node (ref "U25") (pin "6") (pinfunction "REF_6") (pintype "passive"))
    )
    (net (code "24") (name "Net-(U25B-~{RESET})") (class "Default")
      (node (ref "C214") (pin "2") (pinfunction "2_2") (pintype "passive"))
      (node (ref "R156") (pin "1") (pinfunction "1_1") (pintype "passive"))
      (node (ref "U25") (pin "14") (pinfunction "~{RESET}_14") (pintype "input"))
    )
    (net (code "25") (name "USB_UART_3V3") (class "Default")
      (node (ref "C207") (pin "2") (pinfunction "2_2") (pintype "passive"))
      (node (ref "C208") (pin "2") (pinfunction "2_2") (pintype "passive"))
      (node (ref "C209") (pin "2") (pinfunction "2_2") (pintype "passive"))
      (node (ref "C210") (pin "2") (pinfunction "2_2") (pintype "passive"))
      (node (ref "C211") (pin "2") (pinfunction "2_2") (pintype "passive"))
      (node (ref "C217") (pin "2") (pinfunction "2_2") (pintype "passive"))
      (node (ref "C223") (pin "2") (pinfunction "2_2") (pintype "passive"))
      (node (ref "FB11") (pin "1") (pinfunction "1_1") (pintype "passive"))
      (node (ref "FB12") (pin "1") (pinfunction "1_1") (pintype "passive"))
      (node (ref "R150") (pin "2") (pinfunction "2_2") (pintype "passive"))
      (node (ref "R151") (pin "2") (pinfunction "2_2") (pintype "passive"))
      (node (ref "R152") (pin "2") (pinfunction "2_2") (pintype "passive"))
      (node (ref "R153") (pin "2") (pinfunction "2_2") (pintype "passive"))
      (node (ref "R156") (pin "2") (pinfunction "2_2") (pintype "passive"))
      (node (ref "U24") (pin "11") (pinfunction "VCC(B)_11") (pintype "passive"))
      (node (ref "U25") (pin "20") (pinfunction "VCCIO_20") (pintype "power_in"))
      (node (ref "U25") (pin "31") (pinfunction "VCCIO_31") (pintype "power_in"))
      (node (ref "U25") (pin "42") (pinfunction "VCCIO_42") (pintype "power_in"))
      (node (ref "U25") (pin "50") (pinfunction "VREGIN_50") (pintype "power_in"))
      (node (ref "U25") (pin "56") (pinfunction "VCCIO_56") (pintype "power_in"))
      (node (ref "U26") (pin "2") (pinfunction "VOUT_2") (pintype "passive"))
      (node (ref "U26") (pin "4") (pinfunction "VOUT_4") (pintype "passive"))
    )
    (net (code "26") (name "VDD_1V8") (class "Default")
      (node (ref "C206") (pin "2") (pinfunction "2_2") (pintype "passive"))
      (node (ref "R138") (pin "2") (pinfunction "2_2") (pintype "passive"))
      (node (ref "R139") (pin "2") (pinfunction "2_2") (pintype "passive"))
      (node (ref "R146") (pin "2") (pinfunction "2_2") (pintype "passive"))
      (node (ref "R147") (pin "2") (pinfunction "2_2") (pintype "passive"))
      (node (ref "R148") (pin "2") (pinfunction "2_2") (pintype "passive"))
      (node (ref "R149") (pin "2") (pinfunction "2_2") (pintype "passive"))
      (node (ref "R154") (pin "1") (pinfunction "1_1") (pintype "passive"))
      (node (ref "U24") (pin "1") (pinfunction "VCC(A)_1") (pintype "passive"))
    )
    (net (code "27") (name "unconnected-(SW1-A1-Pad1)") (class "Default")
      (node (ref "SW1") (pin "1") (pinfunction "A1_1") (pintype "passive+no_connect"))
    )
    (net (code "28") (name "unconnected-(SW1-A2-Pad2)") (class "Default")
      (node (ref "SW1") (pin "2") (pinfunction "A2_2") (pintype "passive+no_connect"))
    )
    (net (code "29") (name "unconnected-(SW1-B1-Pad8)") (class "Default")
      (node (ref "SW1") (pin "8") (pinfunction "B1_8") (pintype "passive+no_connect"))
    )
    (net (code "30") (name "unconnected-(SW1-B2-Pad7)") (class "Default")
      (node (ref "SW1") (pin "7") (pinfunction "B2_7") (pintype "passive+no_connect"))
    )
    (net (code "31") (name "unconnected-(U25B-ACBUS0-Pad26)") (class "Default")
      (node (ref "U25") (pin "26") (pinfunction "ACBUS0_26") (pintype "bidirectional"))
    )
    (net (code "32") (name "unconnected-(U25B-ACBUS1-Pad27)") (class "Default")
      (node (ref "U25") (pin "27") (pinfunction "ACBUS1_27") (pintype "bidirectional"))
    )
    (net (code "33") (name "unconnected-(U25B-ACBUS2-Pad28)") (class "Default")
      (node (ref "U25") (pin "28") (pinfunction "ACBUS2_28") (pintype "bidirectional"))
    )
    (net (code "34") (name "unconnected-(U25B-ACBUS3-Pad29)") (class "Default")
      (node (ref "U25") (pin "29") (pinfunction "ACBUS3_29") (pintype "bidirectional"))
    )
    (net (code "35") (name "unconnected-(U25B-ACBUS4-Pad30)") (class "Default")
      (node (ref "U25") (pin "30") (pinfunction "ACBUS4_30") (pintype "bidirectional"))
    )
    (net (code "36") (name "unconnected-(U25B-ACBUS5-Pad32)") (class "Default")
      (node (ref "U25") (pin "32") (pinfunction "ACBUS5_32") (pintype "bidirectional"))
    )
    (net (code "37") (name "unconnected-(U25B-ACBUS6-Pad33)") (class "Default")
      (node (ref "U25") (pin "33") (pinfunction "ACBUS6_33") (pintype "bidirectional"))
    )
    (net (code "38") (name "unconnected-(U25B-ACBUS7-Pad34)") (class "Default")
      (node (ref "U25") (pin "34") (pinfunction "ACBUS7_34") (pintype "bidirectional"))
    )
    (net (code "39") (name "unconnected-(U25B-ADBUS2-Pad18)") (class "Default")
      (node (ref "U25") (pin "18") (pinfunction "ADBUS2_18") (pintype "bidirectional"))
    )
    (net (code "40") (name "unconnected-(U25B-ADBUS3-Pad19)") (class "Default")
      (node (ref "U25") (pin "19") (pinfunction "ADBUS3_19") (pintype "bidirectional"))
    )
    (net (code "41") (name "unconnected-(U25B-ADBUS4-Pad21)") (class "Default")
      (node (ref "U25") (pin "21") (pinfunction "ADBUS4_21") (pintype "bidirectional"))
    )
    (net (code "42") (name "unconnected-(U25B-ADBUS5-Pad22)") (class "Default")
      (node (ref "U25") (pin "22") (pinfunction "ADBUS5_22") (pintype "bidirectional"))
    )
    (net (code "43") (name "unconnected-(U25B-ADBUS6-Pad23)") (class "Default")
      (node (ref "U25") (pin "23") (pinfunction "ADBUS6_23") (pintype "bidirectional"))
    )
    (net (code "44") (name "unconnected-(U25B-ADBUS7-Pad24)") (class "Default")
      (node (ref "U25") (pin "24") (pinfunction "ADBUS7_24") (pintype "bidirectional"))
    )
    (net (code "45") (name "unconnected-(U25B-BCBUS0-Pad48)") (class "Default")
      (node (ref "U25") (pin "48") (pinfunction "BCBUS0_48") (pintype "bidirectional"))
    )
    (net (code "46") (name "unconnected-(U25B-BCBUS1-Pad52)") (class "Default")
      (node (ref "U25") (pin "52") (pinfunction "BCBUS1_52") (pintype "bidirectional"))
    )
    (net (code "47") (name "unconnected-(U25B-BCBUS2-Pad53)") (class "Default")
      (node (ref "U25") (pin "53") (pinfunction "BCBUS2_53") (pintype "bidirectional"))
    )
    (net (code "48") (name "unconnected-(U25B-BCBUS3-Pad54)") (class "Default")
      (node (ref "U25") (pin "54") (pinfunction "BCBUS3_54") (pintype "bidirectional"))
    )
    (net (code "49") (name "unconnected-(U25B-BCBUS4-Pad55)") (class "Default")
      (node (ref "U25") (pin "55") (pinfunction "BCBUS4_55") (pintype "bidirectional"))
    )
    (net (code "50") (name "unconnected-(U25B-BCBUS5-Pad57)") (class "Default")
      (node (ref "U25") (pin "57") (pinfunction "BCBUS5_57") (pintype "bidirectional"))
    )
    (net (code "51") (name "unconnected-(U25B-BCBUS6-Pad58)") (class "Default")
      (node (ref "U25") (pin "58") (pinfunction "BCBUS6_58") (pintype "bidirectional"))
    )
    (net (code "52") (name "unconnected-(U25B-BCBUS7-Pad59)") (class "Default")
      (node (ref "U25") (pin "59") (pinfunction "BCBUS7_59") (pintype "bidirectional"))
    )
    (net (code "53") (name "unconnected-(U25B-BDBUS2-Pad40)") (class "Default")
      (node (ref "U25") (pin "40") (pinfunction "BDBUS2_40") (pintype "bidirectional"))
    )
    (net (code "54") (name "unconnected-(U25B-BDBUS3-Pad41)") (class "Default")
      (node (ref "U25") (pin "41") (pinfunction "BDBUS3_41") (pintype "bidirectional"))
    )
    (net (code "55") (name "unconnected-(U25B-BDBUS4-Pad43)") (class "Default")
      (node (ref "U25") (pin "43") (pinfunction "BDBUS4_43") (pintype "bidirectional"))
    )
    (net (code "56") (name "unconnected-(U25B-BDBUS5-Pad44)") (class "Default")
      (node (ref "U25") (pin "44") (pinfunction "BDBUS5_44") (pintype "bidirectional"))
    )
    (net (code "57") (name "unconnected-(U25B-BDBUS6-Pad45)") (class "Default")
      (node (ref "U25") (pin "45") (pinfunction "BDBUS6_45") (pintype "bidirectional"))
    )
    (net (code "58") (name "unconnected-(U25B-BDBUS7-Pad46)") (class "Default")
      (node (ref "U25") (pin "46") (pinfunction "BDBUS7_46") (pintype "bidirectional"))
    )
    (net (code "59") (name "unconnected-(U25B-EECLK-Pad62)") (class "Default")
      (node (ref "U25") (pin "62") (pinfunction "EECLK_62") (pintype "output+no_connect"))
    )
    (net (code "60") (name "unconnected-(U25B-EECS-Pad63)") (class "Default")
      (node (ref "U25") (pin "63") (pinfunction "EECS_63") (pintype "bidirectional+no_connect"))
    )
    (net (code "61") (name "unconnected-(U25B-EEDATA-Pad61)") (class "Default")
      (node (ref "U25") (pin "61") (pinfunction "EEDATA_61") (pintype "bidirectional+no_connect"))
    )
    (net (code "62") (name "unconnected-(U25B-~{PWREN}-Pad60)") (class "Default")
      (node (ref "U25") (pin "60") (pinfunction "~{PWREN}_60") (pintype "output"))
    )
    (net (code "63") (name "unconnected-(U25B-~{SUSPEND}-Pad36)") (class "Default")
      (node (ref "U25") (pin "36") (pinfunction "~{SUSPEND}_36") (pintype "output"))
    )
  )
)
